# MCU.net
KiCad netlist of a schematic drawn in Altium Designer
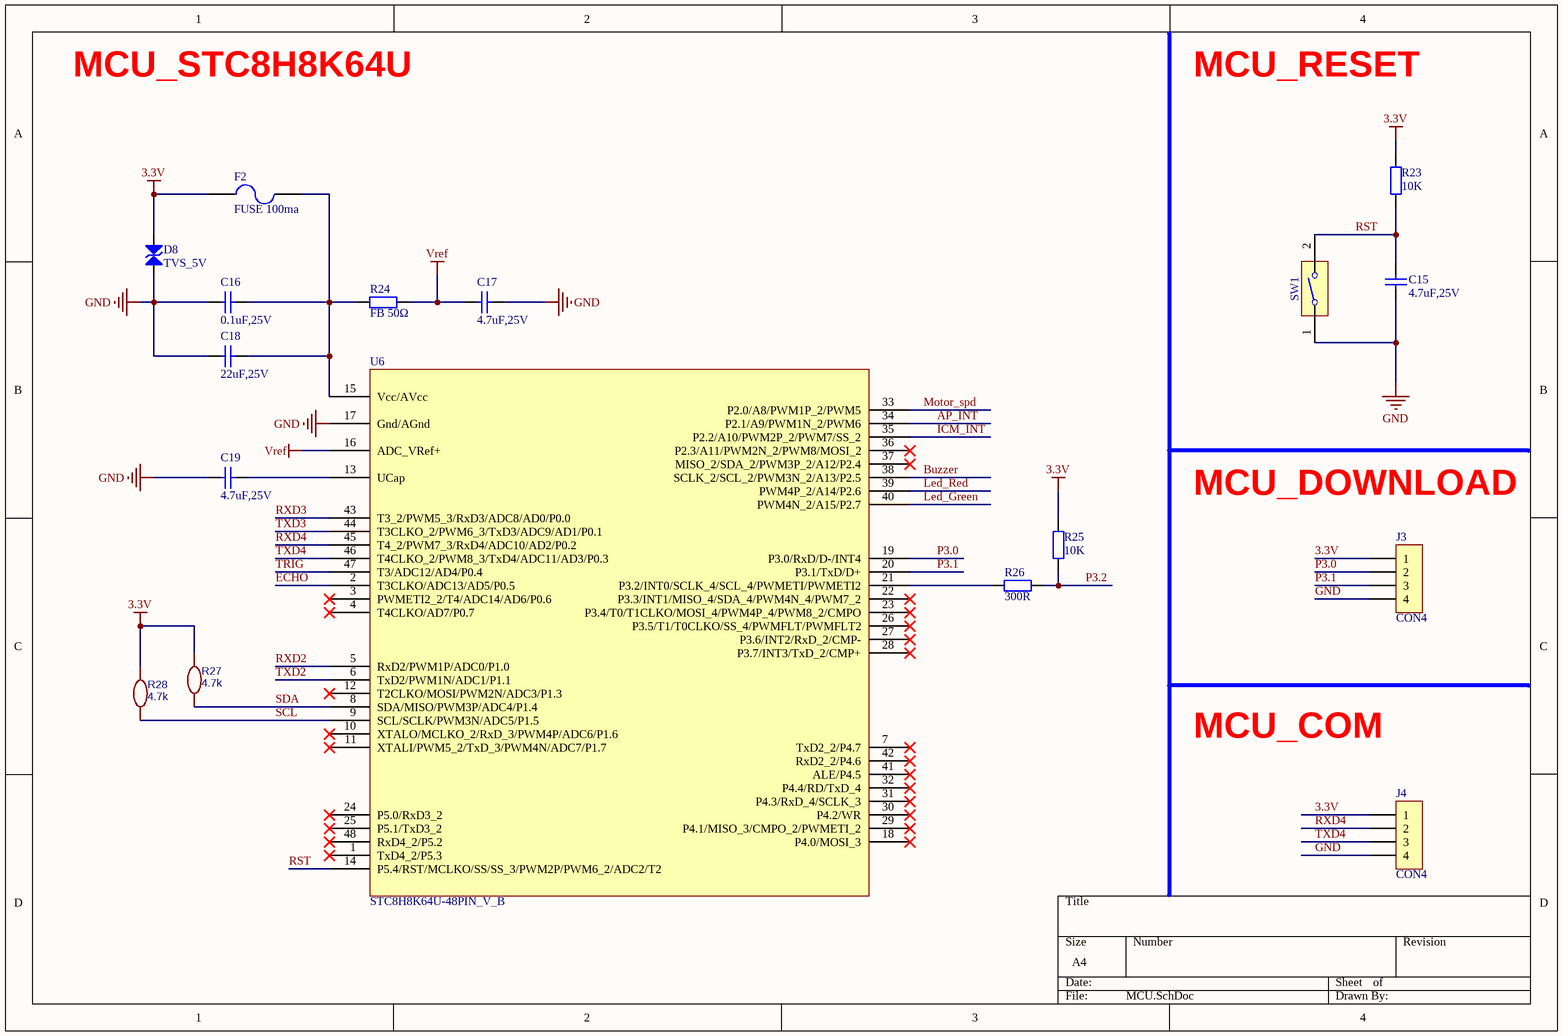
[diagram p0: MCU.SchDoc]

(export (version "E")
  (design (tool "Eeschema 10.0.6"))
  (components
    (comp (ref "C15")
      (value "4.7uF,25V")
      (footprint "0603_C")
      (description "贴片电容")
      (fields (field (name "PART NUMBER") "T_Cap_0603_2.2uF_25V_Y5V") (field (name "TOLERANCE") "20%"))
      (libsource (lib "Database_Library") (part "Cap"))
    )
    (comp (ref "C16")
      (value "0.1uF,25V")
      (footprint "0603_C")
      (description "贴片电容")
      (fields (field (name "PART NUMBER") "T_Cap_0603_2.2uF_25V_Y5V") (field (name "TOLERANCE") "20%"))
      (libsource (lib "Database_Library") (part "Cap"))
    )
    (comp (ref "C17")
      (value "4.7uF,25V")
      (footprint "0603_C")
      (description "贴片电容")
      (fields (field (name "PART NUMBER") "T_Cap_0603_2.2uF_25V_Y5V") (field (name "TOLERANCE") "20%"))
      (libsource (lib "Database_Library") (part "Cap"))
    )
    (comp (ref "C18")
      (value "22uF,25V")
      (footprint "0603_C")
      (description "贴片电容")
      (fields (field (name "PART NUMBER") "T_Cap_0603_2.2uF_25V_Y5V") (field (name "TOLERANCE") "20%"))
      (libsource (lib "Database_Library") (part "Cap"))
    )
    (comp (ref "C19")
      (value "4.7uF,25V")
      (footprint "0603_C")
      (description "贴片电容")
      (fields (field (name "PART NUMBER") "T_Cap_0603_2.2uF_25V_Y5V") (field (name "TOLERANCE") "20%"))
      (libsource (lib "Database_Library") (part "Cap"))
    )
    (comp (ref "D8")
      (value "TVS_5V")
      (footprint "SOD-323")
      (description "TVS,ESD二极管")
      (libsource (lib "aiskylab-04Dio-1K") (part "TBV05C"))
    )
    (comp (ref "F2")
      (value "FUSE 100ma")
      (footprint "1206_FUSE")
      (description "Fuse")
      (fields (field (name "PUBLISHER") "Altium Limited"))
      (libsource (lib "jinrylib") (part "Fuse 2"))
    )
    (comp (ref "J3") (value "CON4") (description "Connector") (libsource (lib "Schlib1") (part "CON4")))
    (comp (ref "J4") (value "CON4") (description "Connector") (libsource (lib "Schlib1") (part "CON4")))
    (comp (ref "R23")
      (value "10K")
      (footprint "0603_R")
      (description "贴片电阻")
      (fields (field (name "PART NUMBER") "T_Res_0603_49.9k_1%_1/10W") (field (name "POWER") "1/10W"))
      (libsource (lib "Database_Library") (part "Res"))
    )
    (comp (ref "R24")
      (value "FB 50Ω")
      (footprint "0603_R")
      (description "贴片电阻")
      (fields (field (name "PART NUMBER") "T_Res_0603_49.9k_1%_1/10W") (field (name "POWER") "1/10W"))
      (libsource (lib "") (part "Res_2"))
    )
    (comp (ref "R25")
      (value "10K")
      (footprint "0603_R")
      (description "贴片电阻")
      (fields (field (name "PART NUMBER") "T_Res_0603_49.9k_1%_1/10W") (field (name "POWER") "1/10W"))
      (libsource (lib "Database_Library") (part "Res"))
    )
    (comp (ref "R26")
      (value "300R")
      (footprint "0603_R")
      (description "贴片电阻")
      (fields (field (name "PART NUMBER") "T_Res_0603_49.9k_1%_1/10W") (field (name "POWER") "1/10W"))
      (libsource (lib "") (part "Res_1"))
    )
    (comp (ref "R27")
      (value "4.7k")
      (footprint "0402_R")
      (fields (field (name "CONTRIBUTOR") "LCEDA_Lib"))
      (libsource (lib "altium-import") (part "root_3_100k_"))
    )
    (comp (ref "R28")
      (value "4.7k")
      (footprint "0402_R")
      (fields (field (name "CONTRIBUTOR") "LCEDA_Lib"))
      (libsource (lib "altium-import") (part "root_3_100k_"))
    )
    (comp (ref "SW1")
      (value "~")
      (description "1 Ways SPST DIP Switch")
      (libsource (lib "aiskylab-11Electromechanical") (part "SW 1x SPST DIP Switch"))
    )
    (comp (ref "U6")
      (value "STC8H8K64U-48PIN_V_B")
      (footprint "QFN48(6X6mm)")
      (libsource (lib "Schlib1") (part "STC8H8K64U-48PIN"))
    )
  )
  (nets
    (net (code "1") (name "/AP_INT") (class "Default")
      (node (ref "U6") (pin "34") (pinfunction "P2.1/A9/PWM1N_2/PWM6_34") (pintype "passive"))
    )
    (net (code "2") (name "/Buzzer") (class "Default")
      (node (ref "U6") (pin "38") (pinfunction "SCLK_2/SCL_2/PWM3N_2/A13/P2.5_38") (pintype "passive"))
    )
    (net (code "3") (name "/ECHO") (class "Default")
      (node (ref "U6") (pin "2") (pinfunction "T3CLKO/ADC13/AD5/P0.5_2") (pintype "passive"))
    )
    (net (code "4") (name "/ICM_INT") (class "Default")
      (node (ref "U6") (pin "35") (pinfunction "P2.2/A10/PWM2P_2/PWM7/SS_2_35") (pintype "passive"))
    )
    (net (code "5") (name "/Led_Green") (class "Default")
      (node (ref "U6") (pin "40") (pinfunction "PWM4N_2/A15/P2.7_40") (pintype "passive"))
    )
    (net (code "6") (name "/Led_Red") (class "Default")
      (node (ref "U6") (pin "39") (pinfunction "PWM4P_2/A14/P2.6_39") (pintype "passive"))
    )
    (net (code "7") (name "/Motor_spd") (class "Default")
      (node (ref "U6") (pin "33") (pinfunction "P2.0/A8/PWM1P_2/PWM5_33") (pintype "passive"))
    )
    (net (code "8") (name "/P3.0") (class "Default")
      (node (ref "J3") (pin "2") (pinfunction "2_2") (pintype "passive"))
      (node (ref "U6") (pin "19") (pinfunction "P3.0/RxD/D-/INT4_19") (pintype "passive"))
    )
    (net (code "9") (name "/P3.1") (class "Default")
      (node (ref "J3") (pin "3") (pinfunction "3_3") (pintype "passive"))
      (node (ref "U6") (pin "20") (pinfunction "P3.1/TxD/D+_20") (pintype "passive"))
    )
    (net (code "10") (name "/P3.2") (class "Default")
      (node (ref "R25") (pin "2") (pinfunction "2_2") (pintype "passive"))
      (node (ref "R26") (pin "2") (pinfunction "2_2") (pintype "passive"))
    )
    (net (code "11") (name "/RST") (class "Default")
      (node (ref "C15") (pin "1") (pinfunction "1_1") (pintype "passive"))
      (node (ref "R23") (pin "2") (pinfunction "2_2") (pintype "passive"))
      (node (ref "SW1") (pin "2") (pinfunction "2_2") (pintype "passive"))
      (node (ref "U6") (pin "14") (pinfunction "P5.4/RST/MCLKO/SS/SS_3/PWM2P/PWM6_2/ADC2/T2_14") (pintype "passive"))
    )
    (net (code "12") (name "/RXD2") (class "Default")
      (node (ref "U6") (pin "5") (pinfunction "RxD2/PWM1P/ADC0/P1.0_5") (pintype "passive"))
    )
    (net (code "13") (name "/RXD3") (class "Default")
      (node (ref "U6") (pin "43") (pinfunction "T3_2/PWM5_3/RxD3/ADC8/AD0/P0.0_43") (pintype "passive"))
    )
    (net (code "14") (name "/RXD4") (class "Default")
      (node (ref "J4") (pin "2") (pinfunction "2_2") (pintype "passive"))
      (node (ref "U6") (pin "45") (pinfunction "T4_2/PWM7_3/RxD4/ADC10/AD2/P0.2_45") (pintype "passive"))
    )
    (net (code "15") (name "/SCL") (class "Default")
      (node (ref "R28") (pin "2") (pinfunction "2_2") (pintype "passive"))
      (node (ref "U6") (pin "9") (pinfunction "SCL/SCLK/PWM3N/ADC5/P1.5_9") (pintype "passive"))
    )
    (net (code "16") (name "/SDA") (class "Default")
      (node (ref "R27") (pin "2") (pinfunction "2_2") (pintype "passive"))
      (node (ref "U6") (pin "8") (pinfunction "SDA/MISO/PWM3P/ADC4/P1.4_8") (pintype "passive"))
    )
    (net (code "17") (name "/TRIG") (class "Default")
      (node (ref "U6") (pin "47") (pinfunction "T3/ADC12/AD4/P0.4_47") (pintype "passive"))
    )
    (net (code "18") (name "/TXD2") (class "Default")
      (node (ref "U6") (pin "6") (pinfunction "TxD2/PWM1N/ADC1/P1.1_6") (pintype "passive"))
    )
    (net (code "19") (name "/TXD3") (class "Default")
      (node (ref "U6") (pin "44") (pinfunction "T3CLKO_2/PWM6_3/TxD3/ADC9/AD1/P0.1_44") (pintype "passive"))
    )
    (net (code "20") (name "/TXD4") (class "Default")
      (node (ref "J4") (pin "3") (pinfunction "3_3") (pintype "passive"))
      (node (ref "U6") (pin "46") (pinfunction "T4CLKO_2/PWM8_3/TxD4/ADC11/AD3/P0.3_46") (pintype "passive"))
    )
    (net (code "21") (name "3.3V") (class "Default")
      (node (ref "D8") (pin "1") (pinfunction "1_1") (pintype "passive"))
      (node (ref "F2") (pin "2") (pinfunction "2_2") (pintype "passive"))
      (node (ref "J3") (pin "1") (pinfunction "1_1") (pintype "passive"))
      (node (ref "J4") (pin "1") (pinfunction "1_1") (pintype "passive"))
      (node (ref "R23") (pin "1") (pinfunction "1_1") (pintype "passive"))
      (node (ref "R25") (pin "1") (pinfunction "1_1") (pintype "passive"))
      (node (ref "R27") (pin "1") (pinfunction "1_1") (pintype "passive"))
      (node (ref "R28") (pin "1") (pinfunction "1_1") (pintype "passive"))
    )
    (net (code "22") (name "GND") (class "Default")
      (node (ref "C15") (pin "2") (pinfunction "2_2") (pintype "passive"))
      (node (ref "C16") (pin "1") (pinfunction "1_1") (pintype "passive"))
      (node (ref "C17") (pin "1") (pinfunction "1_1") (pintype "passive"))
      (node (ref "C18") (pin "1") (pinfunction "1_1") (pintype "passive"))
      (node (ref "C19") (pin "2") (pinfunction "2_2") (pintype "passive"))
      (node (ref "D8") (pin "2") (pinfunction "2_2") (pintype "passive"))
      (node (ref "J3") (pin "4") (pinfunction "4_4") (pintype "passive"))
      (node (ref "J4") (pin "4") (pinfunction "4_4") (pintype "passive"))
      (node (ref "SW1") (pin "1") (pinfunction "1_1") (pintype "passive"))
      (node (ref "U6") (pin "17") (pinfunction "Gnd/AGnd_17") (pintype "passive"))
    )
    (net (code "23") (name "Net-(U6-P3.2{slash}INT0{slash}SCLK_4{slash}SCL_4{slash}PWMETI{slash}PWMETI2)") (class "Default")
      (node (ref "R26") (pin "1") (pinfunction "1_1") (pintype "passive"))
      (node (ref "U6") (pin "21") (pinfunction "P3.2/INT0/SCLK_4/SCL_4/PWMETI/PWMETI2_21") (pintype "passive"))
    )
    (net (code "24") (name "Net-(U6-UCap)") (class "Default")
      (node (ref "C19") (pin "1") (pinfunction "1_1") (pintype "passive"))
      (node (ref "U6") (pin "13") (pinfunction "UCap_13") (pintype "passive"))
    )
    (net (code "25") (name "Net-(U6-Vcc{slash}AVcc)") (class "Default")
      (node (ref "C16") (pin "2") (pinfunction "2_2") (pintype "passive"))
      (node (ref "C18") (pin "2") (pinfunction "2_2") (pintype "passive"))
      (node (ref "F2") (pin "1") (pinfunction "1_1") (pintype "passive"))
      (node (ref "R24") (pin "2") (pinfunction "2_2") (pintype "passive"))
      (node (ref "U6") (pin "15") (pinfunction "Vcc/AVcc_15") (pintype "passive"))
    )
    (net (code "26") (name "Vref") (class "Default")
      (node (ref "C17") (pin "2") (pinfunction "2_2") (pintype "passive"))
      (node (ref "R24") (pin "1") (pinfunction "1_1") (pintype "passive"))
      (node (ref "U6") (pin "16") (pinfunction "ADC_VRef+_16") (pintype "passive"))
    )
    (net (code "27") (name "unconnected-(U6-ALE{slash}P4.5-Pad41)") (class "Default")
      (node (ref "U6") (pin "41") (pinfunction "ALE/P4.5_41") (pintype "passive+no_connect"))
    )
    (net (code "28") (name "unconnected-(U6-MISO_2{slash}SDA_2{slash}PWM3P_2{slash}A12{slash}P2.4-Pad37)") (class "Default")
      (node (ref "U6") (pin "37") (pinfunction "MISO_2/SDA_2/PWM3P_2/A12/P2.4_37") (pintype "passive+no_connect"))
    )
    (net (code "29") (name "unconnected-(U6-P2.3{slash}A11{slash}PWM2N_2{slash}PWM8{slash}MOSI_2-Pad36)") (class "Default")
      (node (ref "U6") (pin "36") (pinfunction "P2.3/A11/PWM2N_2/PWM8/MOSI_2_36") (pintype "passive+no_connect"))
    )
    (net (code "30") (name "unconnected-(U6-P3.3{slash}INT1{slash}MISO_4{slash}SDA_4{slash}PWM4N_4{slash}PWM7_2-Pad22)") (class "Default")
      (node (ref "U6") (pin "22") (pinfunction "P3.3/INT1/MISO_4/SDA_4/PWM4N_4/PWM7_2_22") (pintype "passive+no_connect"))
    )
    (net (code "31") (name "unconnected-(U6-P3.4{slash}T0{slash}T1CLKO{slash}MOSI_4{slash}PWM4P_4{slash}PWM8_2{slash}CMPO-Pad23)") (class "Default")
      (node (ref "U6") (pin "23") (pinfunction "P3.4/T0/T1CLKO/MOSI_4/PWM4P_4/PWM8_2/CMPO_23") (pintype "passive+no_connect"))
    )
    (net (code "32") (name "unconnected-(U6-P3.5{slash}T1{slash}T0CLKO{slash}SS_4{slash}PWMFLT{slash}PWMFLT2-Pad26)") (class "Default")
      (node (ref "U6") (pin "26") (pinfunction "P3.5/T1/T0CLKO/SS_4/PWMFLT/PWMFLT2_26") (pintype "passive+no_connect"))
    )
    (net (code "33") (name "unconnected-(U6-P3.6{slash}INT2{slash}RxD_2{slash}CMP--Pad27)") (class "Default")
      (node (ref "U6") (pin "27") (pinfunction "P3.6/INT2/RxD_2/CMP-_27") (pintype "passive+no_connect"))
    )
    (net (code "34") (name "unconnected-(U6-P3.7{slash}INT3{slash}TxD_2{slash}CMP+-Pad28)") (class "Default")
      (node (ref "U6") (pin "28") (pinfunction "P3.7/INT3/TxD_2/CMP+_28") (pintype "passive+no_connect"))
    )
    (net (code "35") (name "unconnected-(U6-P4.0{slash}MOSI_3-Pad18)") (class "Default")
      (node (ref "U6") (pin "18") (pinfunction "P4.0/MOSI_3_18") (pintype "passive+no_connect"))
    )
    (net (code "36") (name "unconnected-(U6-P4.1{slash}MISO_3{slash}CMPO_2{slash}PWMETI_2-Pad29)") (class "Default")
      (node (ref "U6") (pin "29") (pinfunction "P4.1/MISO_3/CMPO_2/PWMETI_2_29") (pintype "passive+no_connect"))
    )
    (net (code "37") (name "unconnected-(U6-P4.2{slash}WR-Pad30)") (class "Default")
      (node (ref "U6") (pin "30") (pinfunction "P4.2/WR_30") (pintype "passive+no_connect"))
    )
    (net (code "38") (name "unconnected-(U6-P4.3{slash}RxD_4{slash}SCLK_3-Pad31)") (class "Default")
      (node (ref "U6") (pin "31") (pinfunction "P4.3/RxD_4/SCLK_3_31") (pintype "passive+no_connect"))
    )
    (net (code "39") (name "unconnected-(U6-P4.4{slash}RD{slash}TxD_4-Pad32)") (class "Default")
      (node (ref "U6") (pin "32") (pinfunction "P4.4/RD/TxD_4_32") (pintype "passive+no_connect"))
    )
    (net (code "40") (name "unconnected-(U6-P5.0{slash}RxD3_2-Pad24)") (class "Default")
      (node (ref "U6") (pin "24") (pinfunction "P5.0/RxD3_2_24") (pintype "passive+no_connect"))
    )
    (net (code "41") (name "unconnected-(U6-P5.1{slash}TxD3_2-Pad25)") (class "Default")
      (node (ref "U6") (pin "25") (pinfunction "P5.1/TxD3_2_25") (pintype "passive+no_connect"))
    )
    (net (code "42") (name "unconnected-(U6-PWMETI2_2{slash}T4{slash}ADC14{slash}AD6{slash}P0.6-Pad3)") (class "Default")
      (node (ref "U6") (pin "3") (pinfunction "PWMETI2_2/T4/ADC14/AD6/P0.6_3") (pintype "passive+no_connect"))
    )
    (net (code "43") (name "unconnected-(U6-RxD2_2{slash}P4.6-Pad42)") (class "Default")
      (node (ref "U6") (pin "42") (pinfunction "RxD2_2/P4.6_42") (pintype "passive+no_connect"))
    )
    (net (code "44") (name "unconnected-(U6-RxD4_2{slash}P5.2-Pad48)") (class "Default")
      (node (ref "U6") (pin "48") (pinfunction "RxD4_2/P5.2_48") (pintype "passive+no_connect"))
    )
    (net (code "45") (name "unconnected-(U6-T2CLKO{slash}MOSI{slash}PWM2N{slash}ADC3{slash}P1.3-Pad12)") (class "Default")
      (node (ref "U6") (pin "12") (pinfunction "T2CLKO/MOSI/PWM2N/ADC3/P1.3_12") (pintype "passive+no_connect"))
    )
    (net (code "46") (name "unconnected-(U6-T4CLKO{slash}AD7{slash}P0.7-Pad4)") (class "Default")
      (node (ref "U6") (pin "4") (pinfunction "T4CLKO/AD7/P0.7_4") (pintype "passive+no_connect"))
    )
    (net (code "47") (name "unconnected-(U6-TxD2_2{slash}P4.7-Pad7)") (class "Default")
      (node (ref "U6") (pin "7") (pinfunction "TxD2_2/P4.7_7") (pintype "passive+no_connect"))
    )
    (net (code "48") (name "unconnected-(U6-TxD4_2{slash}P5.3-Pad1)") (class "Default")
      (node (ref "U6") (pin "1") (pinfunction "TxD4_2/P5.3_1") (pintype "passive+no_connect"))
    )
    (net (code "49") (name "unconnected-(U6-XTALI{slash}PWM5_2{slash}TxD_3{slash}PWM4N{slash}ADC7{slash}P1.7-Pad11)") (class "Default")
      (node (ref "U6") (pin "11") (pinfunction "XTALI/PWM5_2/TxD_3/PWM4N/ADC7/P1.7_11") (pintype "passive+no_connect"))
    )
    (net (code "50") (name "unconnected-(U6-XTALO{slash}MCLKO_2{slash}RxD_3{slash}PWM4P{slash}ADC6{slash}P1.6-Pad10)") (class "Default")
      (node (ref "U6") (pin "10") (pinfunction "XTALO/MCLKO_2/RxD_3/PWM4P/ADC6/P1.6_10") (pintype "passive+no_connect"))
    )
  )
)
